# medusaCharger.net
KiCad netlist of a schematic drawn in Altium Designer
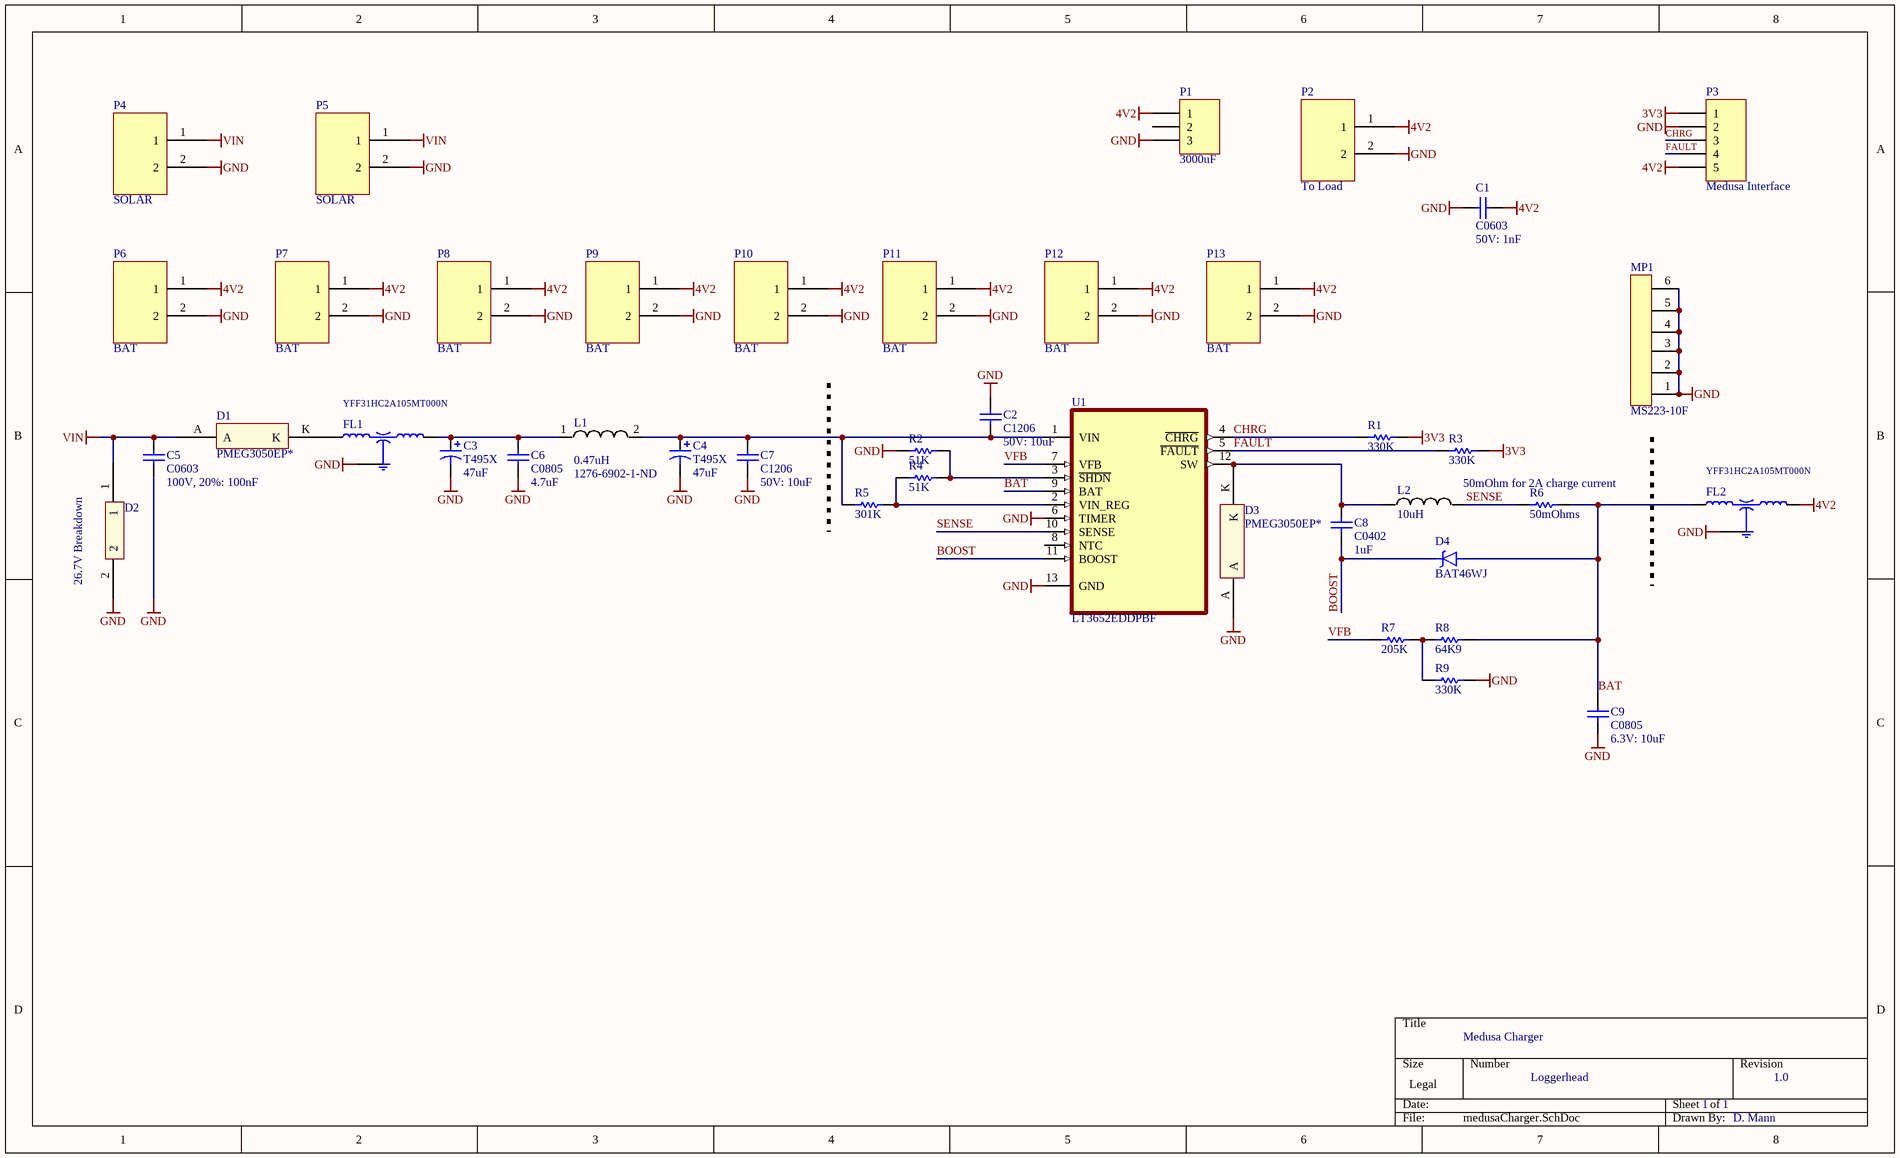
[diagram p0: medusaCharger.SchDoc]

(export (version "E")
  (design (tool "Eeschema 10.0.6"))
  (components
    (comp (ref "C1")
      (value "C0603")
      (footprint "0603")
      (description "Ceramic Chip Capacitor - Standard")
      (fields (field (name "50V") "1nF") (field (name "PUBLISHER") "Altium Limited"))
      (libsource (lib "KEMET Chip Capacitor") (part "C0603"))
    )
    (comp (ref "C2")
      (value "C1206")
      (footprint "1206")
      (description "Ceramic Chip Capacitor - Standard")
      (fields (field (name "50V") "10uF") (field (name "PUBLISHER") "Altium Limited"))
      (libsource (lib "KEMET Chip Capacitor") (part "C1206"))
    )
    (comp (ref "C3")
      (value "T495X")
      (footprint "X")
      (description "Solid Tantalum Chip Capacitor, Standard T495 Series - 35V 10%")
      (fields (field (name "ALTIUM_VALUE") "47uF") (field (name "PUBLISHER") "Altium Limited"))
      (libsource (lib "KEMET Chip Capacitor") (part "T495X"))
    )
    (comp (ref "C4")
      (value "T495X")
      (footprint "X")
      (description "Solid Tantalum Chip Capacitor, Standard T495 Series - 35V 10%")
      (fields (field (name "ALTIUM_VALUE") "47uF") (field (name "PUBLISHER") "Altium Limited"))
      (libsource (lib "KEMET Chip Capacitor") (part "T495X"))
    )
    (comp (ref "C5")
      (value "C0603")
      (footprint "0603")
      (description "100V 20%")
      (fields (field (name "100V, 20%") "100nF") (field (name "PUBLISHER") "Altium Limited"))
      (libsource (lib "KEMET Chip Capacitor") (part "C0603"))
    )
    (comp (ref "C6")
      (value "C0805")
      (footprint "0805")
      (description "Ceramic Chip Capacitor - Standard")
      (fields (field (name "ALTIUM_VALUE") "4.7uF") (field (name "PUBLISHER") "Altium Limited"))
      (libsource (lib "KEMET Chip Capacitor") (part "C0805"))
    )
    (comp (ref "C7")
      (value "C1206")
      (footprint "1206")
      (description "Ceramic Chip Capacitor - Standard")
      (fields (field (name "50V") "10uF") (field (name "PUBLISHER") "Altium Limited"))
      (libsource (lib "KEMET Chip Capacitor") (part "C1206"))
    )
    (comp (ref "C8")
      (value "C0402")
      (footprint "0402")
      (description "Ceramic Chip Capacitor - Standard")
      (fields (field (name "ALTIUM_VALUE") "1uF") (field (name "PUBLISHER") "Altium Limited"))
      (libsource (lib "KEMET Chip Capacitor") (part "C0402"))
    )
    (comp (ref "C9")
      (value "C0805")
      (footprint "0805")
      (description "Ceramic Chip Capacitor - Standard")
      (fields (field (name "6.3V") "10uF") (field (name "PUBLISHER") "Altium Limited"))
      (libsource (lib "KEMET Chip Capacitor") (part "C0805"))
    )
    (comp (ref "D1")
      (value "PMEG3050EP*")
      (footprint "Diode_PMEG3050EP")
      (libsource (lib "") (part "Diode_PMEG3050EP_1"))
    )
    (comp (ref "D2")
      (value "26.7V Breakdown")
      (footprint "SMBJ24CA")
      (libsource (lib "Loggerhead") (part "SMBJ24CA"))
    )
    (comp (ref "D3")
      (value "PMEG3050EP*")
      (footprint "Diode_PMEG3050EP")
      (libsource (lib "Loggerhead") (part "Diode_PMEG3050EP"))
    )
    (comp (ref "D4")
      (value "BAT46WJ")
      (footprint "SOD-323")
      (description "Diode Schottky 100V 250mA (DC) Surface Mount SOD-323F")
      (fields (field (name "MF") "NXP Semiconductors"))
      (libsource (lib "BAT46WJ") (part "BAT46WJ"))
    )
    (comp (ref "FL1")
      (value "YFF31HC2A105MT000N")
      (footprint "FIL_YFF31HC2A105MT000N")
      (description "1ÂµF Feed Through Capacitor 100V 6A 5mOhm 1206 (3216 Metric), 4 PC Pad")
      (fields (field (name "MF") "TDK"))
      (libsource (lib "YFF31HC2A105MT000N") (part "YFF31HC2A105MT000N"))
    )
    (comp (ref "FL2")
      (value "YFF31HC2A105MT000N")
      (footprint "FIL_YFF31HC2A105MT000N")
      (description "1ÂµF Feed Through Capacitor 100V 6A 5mOhm 1206 (3216 Metric), 4 PC Pad")
      (fields (field (name "MF") "TDK"))
      (libsource (lib "YFF31HC2A105MT000N") (part "YFF31HC2A105MT000N"))
    )
    (comp (ref "L1")
      (value "0.47uH")
      (footprint "Inductor2016")
      (fields
        (field (name "SUPPLIER PART NUMBER 1") "1276-6902-1-ND")
        (field (name "Comment") "Inductor2016")
      )
      (libsource (lib "Loggerhead") (part "Inductor2016"))
    )
    (comp (ref "L2")
      (value "10uH")
      (footprint "Inductor0630CDMCD")
      (libsource (lib "Loggerhead") (part "Inductor_0630CDMCD"))
    )
    (comp (ref "MP1")
      (value "MS223-10F")
      (footprint "MS223-10F")
      (description "RF Shield")
      (libsource (lib "Loggerhead") (part "MS223-10F"))
    )
    (comp (ref "P1")
      (value "3000uF")
      (footprint "HDR1X3")
      (description "Header, 3-Pin")
      (fields (field (name "PUBLISHER") "Altium Limited"))
      (libsource (lib "Miscellaneous Connectors") (part "Header 3"))
    )
    (comp (ref "P2")
      (value "To Load")
      (footprint "HDR_2x1_2mm")
      (libsource (lib "Loggerhead") (part "HDR_2x1_2mm"))
    )
    (comp (ref "P3")
      (value "Medusa Interface")
      (footprint "HDR1X5")
      (description "Header, 5-Pin")
      (fields (field (name "PUBLISHER") "Altium Limited"))
      (libsource (lib "Miscellaneous Connectors") (part "Header 5"))
    )
    (comp (ref "P4")
      (value "SOLAR")
      (footprint "HDR_2x1_2mm")
      (libsource (lib "Loggerhead") (part "HDR_2x1_2mm"))
    )
    (comp (ref "P5")
      (value "SOLAR")
      (footprint "HDR_2x1_2mm")
      (libsource (lib "Loggerhead") (part "HDR_2x1_2mm"))
    )
    (comp (ref "P6")
      (value "BAT")
      (footprint "HDR_2x1_2mm")
      (libsource (lib "Loggerhead") (part "HDR_2x1_2mm"))
    )
    (comp (ref "P7")
      (value "BAT")
      (footprint "HDR_2x1_2mm")
      (libsource (lib "Loggerhead") (part "HDR_2x1_2mm"))
    )
    (comp (ref "P8")
      (value "BAT")
      (footprint "HDR_2x1_2mm")
      (libsource (lib "Loggerhead") (part "HDR_2x1_2mm"))
    )
    (comp (ref "P9")
      (value "BAT")
      (footprint "HDR_2x1_2mm")
      (libsource (lib "Loggerhead") (part "HDR_2x1_2mm"))
    )
    (comp (ref "P10")
      (value "BAT")
      (footprint "HDR_2x1_2mm")
      (libsource (lib "Loggerhead") (part "HDR_2x1_2mm"))
    )
    (comp (ref "P11")
      (value "BAT")
      (footprint "HDR_2x1_2mm")
      (libsource (lib "Loggerhead") (part "HDR_2x1_2mm"))
    )
    (comp (ref "P12")
      (value "BAT")
      (footprint "HDR_2x1_2mm")
      (libsource (lib "Loggerhead") (part "HDR_2x1_2mm"))
    )
    (comp (ref "P13")
      (value "BAT")
      (footprint "HDR_2x1_2mm")
      (libsource (lib "Loggerhead") (part "HDR_2x1_2mm"))
    )
    (comp (ref "R1")
      (value "330K")
      (footprint "3-0603")
      (fields (field (name "PUBLISHER") "Altium Limited"))
      (libsource (lib "Panasonic Resistor") (part "ERJ3EK"))
    )
    (comp (ref "R2")
      (value "51K")
      (footprint "3-0603")
      (fields (field (name "PUBLISHER") "Altium Limited"))
      (libsource (lib "Panasonic Resistor") (part "ERJ3EK"))
    )
    (comp (ref "R3")
      (value "330K")
      (footprint "3-0603")
      (fields (field (name "PUBLISHER") "Altium Limited"))
      (libsource (lib "Panasonic Resistor") (part "ERJ3EK"))
    )
    (comp (ref "R4")
      (value "51K")
      (footprint "3-0603")
      (fields (field (name "PUBLISHER") "Altium Limited"))
      (libsource (lib "Panasonic Resistor") (part "ERJ3EK"))
    )
    (comp (ref "R5")
      (value "301K")
      (footprint "3-0603")
      (fields (field (name "PUBLISHER") "Altium Limited"))
      (libsource (lib "Panasonic Resistor") (part "ERJ3EK"))
    )
    (comp (ref "R6")
      (value "50mOhms")
      (footprint "8-1206")
      (description "Precision Thick Film Chip Resistor, 10 Ohm to 2.2M Ohm Range, 1% Tolerance, 1206 Size, 0.125 W")
      (fields (field (name "PUBLISHER") "Altium Limited"))
      (libsource (lib "Panasonic Resistor") (part "ERJ8EN"))
    )
    (comp (ref "R7")
      (value "205K")
      (footprint "3-0603")
      (fields (field (name "PUBLISHER") "Altium Limited"))
      (libsource (lib "Panasonic Resistor") (part "ERJ3EK"))
    )
    (comp (ref "R8")
      (value "64K9")
      (footprint "3-0603")
      (fields (field (name "PUBLISHER") "Altium Limited"))
      (libsource (lib "Panasonic Resistor") (part "ERJ3EK"))
    )
    (comp (ref "R9")
      (value "330K")
      (footprint "3-0603")
      (fields (field (name "PUBLISHER") "Altium Limited"))
      (libsource (lib "Panasonic Resistor") (part "ERJ3EK"))
    )
    (comp (ref "U1")
      (value "LT3652EDDPBF")
      (footprint "DFN300X300X80-13N")
      (description "Power Tracking 2A Battery Charger for Solar Power")
      (libsource (lib "LT3652EDDPBF") (part "LT3652EDDPBF"))
    )
  )
  (nets
    (net (code "1") (name "/BAT") (class "Default")
      (node (ref "C9") (pin "2") (pinfunction "2_2") (pintype "passive"))
      (node (ref "D4") (pin "A") (pinfunction "A_A") (pintype "passive"))
      (node (ref "FL2") (pin "1") (pinfunction "IN/OUT_1") (pintype "passive"))
      (node (ref "R6") (pin "2") (pinfunction "2_2") (pintype "passive"))
      (node (ref "R8") (pin "1") (pinfunction "1_1") (pintype "passive"))
      (node (ref "U1") (pin "9") (pinfunction "BAT_9") (pintype "input"))
    )
    (net (code "2") (name "/BOOST") (class "Default")
      (node (ref "C8") (pin "1") (pinfunction "1_1") (pintype "passive"))
      (node (ref "D4") (pin "C") (pinfunction "C_C") (pintype "passive"))
      (node (ref "U1") (pin "11") (pinfunction "BOOST_11") (pintype "input"))
    )
    (net (code "3") (name "/CHRG") (class "Default")
      (node (ref "P3") (pin "3") (pinfunction "3_3") (pintype "passive"))
      (node (ref "R1") (pin "2") (pinfunction "2_2") (pintype "passive"))
      (node (ref "U1") (pin "4") (pinfunction "~{CHRG}_4") (pintype "output"))
    )
    (net (code "4") (name "/FAULT") (class "Default")
      (node (ref "P3") (pin "4") (pinfunction "4_4") (pintype "passive"))
      (node (ref "R3") (pin "2") (pinfunction "2_2") (pintype "passive"))
      (node (ref "U1") (pin "5") (pinfunction "~{FAULT}_5") (pintype "output"))
    )
    (net (code "5") (name "/SENSE") (class "Default")
      (node (ref "L2") (pin "2") (pinfunction "2_2") (pintype "passive"))
      (node (ref "R6") (pin "1") (pinfunction "1_1") (pintype "passive"))
      (node (ref "U1") (pin "10") (pinfunction "SENSE_10") (pintype "input"))
    )
    (net (code "6") (name "/VFB") (class "Default")
      (node (ref "R7") (pin "2") (pinfunction "2_2") (pintype "passive"))
      (node (ref "U1") (pin "7") (pinfunction "VFB_7") (pintype "input"))
    )
    (net (code "7") (name "3V3") (class "Default")
      (node (ref "P3") (pin "1") (pinfunction "1_1") (pintype "passive"))
      (node (ref "R1") (pin "1") (pinfunction "1_1") (pintype "passive"))
      (node (ref "R3") (pin "1") (pinfunction "1_1") (pintype "passive"))
    )
    (net (code "8") (name "4V2") (class "Default")
      (node (ref "C1") (pin "2") (pinfunction "2_2") (pintype "passive"))
      (node (ref "FL2") (pin "3") (pinfunction "OUT/IN_3") (pintype "passive"))
      (node (ref "P1") (pin "1") (pinfunction "1_1") (pintype "passive"))
      (node (ref "P10") (pin "1") (pinfunction "1_1") (pintype "passive"))
      (node (ref "P11") (pin "1") (pinfunction "1_1") (pintype "passive"))
      (node (ref "P12") (pin "1") (pinfunction "1_1") (pintype "passive"))
      (node (ref "P13") (pin "1") (pinfunction "1_1") (pintype "passive"))
      (node (ref "P2") (pin "1") (pinfunction "1_1") (pintype "passive"))
      (node (ref "P3") (pin "5") (pinfunction "5_5") (pintype "passive"))
      (node (ref "P6") (pin "1") (pinfunction "1_1") (pintype "passive"))
      (node (ref "P7") (pin "1") (pinfunction "1_1") (pintype "passive"))
      (node (ref "P8") (pin "1") (pinfunction "1_1") (pintype "passive"))
      (node (ref "P9") (pin "1") (pinfunction "1_1") (pintype "passive"))
    )
    (net (code "9") (name "GND") (class "Default")
      (node (ref "C1") (pin "1") (pinfunction "1_1") (pintype "passive"))
      (node (ref "C2") (pin "1") (pinfunction "1_1") (pintype "passive"))
      (node (ref "C3") (pin "2") (pinfunction "2_2") (pintype "passive"))
      (node (ref "C4") (pin "2") (pinfunction "2_2") (pintype "passive"))
      (node (ref "C5") (pin "1") (pinfunction "1_1") (pintype "passive"))
      (node (ref "C6") (pin "1") (pinfunction "1_1") (pintype "passive"))
      (node (ref "C7") (pin "1") (pinfunction "1_1") (pintype "passive"))
      (node (ref "C9") (pin "1") (pinfunction "1_1") (pintype "passive"))
      (node (ref "D2") (pin "2") (pinfunction "2_2") (pintype "passive"))
      (node (ref "D3") (pin "A") (pinfunction "A_A") (pintype "passive"))
      (node (ref "FL1") (pin "2_4") (pinfunction "GND_2_4") (pintype "power_in"))
      (node (ref "FL2") (pin "2_4") (pinfunction "GND_2_4") (pintype "power_in"))
      (node (ref "MP1") (pin "1") (pinfunction "1_1") (pintype "passive"))
      (node (ref "MP1") (pin "2") (pinfunction "2_2") (pintype "passive"))
      (node (ref "MP1") (pin "3") (pinfunction "3_3") (pintype "passive"))
      (node (ref "MP1") (pin "4") (pinfunction "4_4") (pintype "passive"))
      (node (ref "MP1") (pin "5") (pinfunction "5_5") (pintype "passive"))
      (node (ref "MP1") (pin "6") (pinfunction "6_6") (pintype "passive"))
      (node (ref "P1") (pin "3") (pinfunction "3_3") (pintype "passive"))
      (node (ref "P10") (pin "2") (pinfunction "2_2") (pintype "passive"))
      (node (ref "P11") (pin "2") (pinfunction "2_2") (pintype "passive"))
      (node (ref "P12") (pin "2") (pinfunction "2_2") (pintype "passive"))
      (node (ref "P13") (pin "2") (pinfunction "2_2") (pintype "passive"))
      (node (ref "P2") (pin "2") (pinfunction "2_2") (pintype "passive"))
      (node (ref "P3") (pin "2") (pinfunction "2_2") (pintype "passive"))
      (node (ref "P4") (pin "2") (pinfunction "2_2") (pintype "passive"))
      (node (ref "P5") (pin "2") (pinfunction "2_2") (pintype "passive"))
      (node (ref "P6") (pin "2") (pinfunction "2_2") (pintype "passive"))
      (node (ref "P7") (pin "2") (pinfunction "2_2") (pintype "passive"))
      (node (ref "P8") (pin "2") (pinfunction "2_2") (pintype "passive"))
      (node (ref "P9") (pin "2") (pinfunction "2_2") (pintype "passive"))
      (node (ref "R2") (pin "1") (pinfunction "1_1") (pintype "passive"))
      (node (ref "R9") (pin "1") (pinfunction "1_1") (pintype "passive"))
      (node (ref "U1") (pin "13") (pinfunction "GND_13") (pintype "passive"))
      (node (ref "U1") (pin "6") (pinfunction "TIMER_6") (pintype "input"))
    )
    (net (code "10") (name "Net-(FL1-IN{slash}OUT)") (class "Default")
      (node (ref "D1") (pin "K") (pinfunction "K_K") (pintype "passive"))
      (node (ref "FL1") (pin "1") (pinfunction "IN/OUT_1") (pintype "passive"))
    )
    (net (code "11") (name "Net-(FL1-OUT{slash}IN)") (class "Default")
      (node (ref "C3") (pin "1") (pinfunction "1_1") (pintype "passive"))
      (node (ref "C6") (pin "2") (pinfunction "2_2") (pintype "passive"))
      (node (ref "FL1") (pin "3") (pinfunction "OUT/IN_3") (pintype "passive"))
      (node (ref "L1") (pin "1") (pinfunction "1_1") (pintype "passive"))
    )
    (net (code "12") (name "Net-(R7-Pad1)") (class "Default")
      (node (ref "R7") (pin "1") (pinfunction "1_1") (pintype "passive"))
      (node (ref "R8") (pin "2") (pinfunction "2_2") (pintype "passive"))
      (node (ref "R9") (pin "2") (pinfunction "2_2") (pintype "passive"))
    )
    (net (code "13") (name "Net-(U1-SW)") (class "Default")
      (node (ref "C8") (pin "2") (pinfunction "2_2") (pintype "passive"))
      (node (ref "D3") (pin "K") (pinfunction "K_K") (pintype "passive"))
      (node (ref "L2") (pin "1") (pinfunction "1_1") (pintype "passive"))
      (node (ref "U1") (pin "12") (pinfunction "SW_12") (pintype "output"))
    )
    (net (code "14") (name "Net-(U1-VIN)") (class "Default")
      (node (ref "C2") (pin "2") (pinfunction "2_2") (pintype "passive"))
      (node (ref "C4") (pin "1") (pinfunction "1_1") (pintype "passive"))
      (node (ref "C7") (pin "2") (pinfunction "2_2") (pintype "passive"))
      (node (ref "L1") (pin "2") (pinfunction "2_2") (pintype "passive"))
      (node (ref "R5") (pin "1") (pinfunction "1_1") (pintype "passive"))
      (node (ref "U1") (pin "1") (pinfunction "VIN_1") (pintype "power_in"))
    )
    (net (code "15") (name "Net-(U1-VIN_REG)") (class "Default")
      (node (ref "R4") (pin "1") (pinfunction "1_1") (pintype "passive"))
      (node (ref "R5") (pin "2") (pinfunction "2_2") (pintype "passive"))
      (node (ref "U1") (pin "2") (pinfunction "VIN_REG_2") (pintype "input"))
    )
    (net (code "16") (name "Net-(U1-~{SHDN})") (class "Default")
      (node (ref "R2") (pin "2") (pinfunction "2_2") (pintype "passive"))
      (node (ref "R4") (pin "2") (pinfunction "2_2") (pintype "passive"))
      (node (ref "U1") (pin "3") (pinfunction "~{SHDN}_3") (pintype "input"))
    )
    (net (code "17") (name "VIN") (class "Default")
      (node (ref "C5") (pin "2") (pinfunction "2_2") (pintype "passive"))
      (node (ref "D1") (pin "A") (pinfunction "A_A") (pintype "passive"))
      (node (ref "D2") (pin "1") (pinfunction "1_1") (pintype "passive"))
      (node (ref "P4") (pin "1") (pinfunction "1_1") (pintype "passive"))
      (node (ref "P5") (pin "1") (pinfunction "1_1") (pintype "passive"))
    )
    (net (code "18") (name "unconnected-(P1-Pad2)") (class "Default")
      (node (ref "P1") (pin "2") (pinfunction "2_2") (pintype "passive"))
    )
    (net (code "19") (name "unconnected-(U1-NTC-Pad8)") (class "Default")
      (node (ref "U1") (pin "8") (pinfunction "NTC_8") (pintype "input"))
    )
  )
)
